# Sheet1.net
KiCad netlist of a schematic drawn in Altium Designer
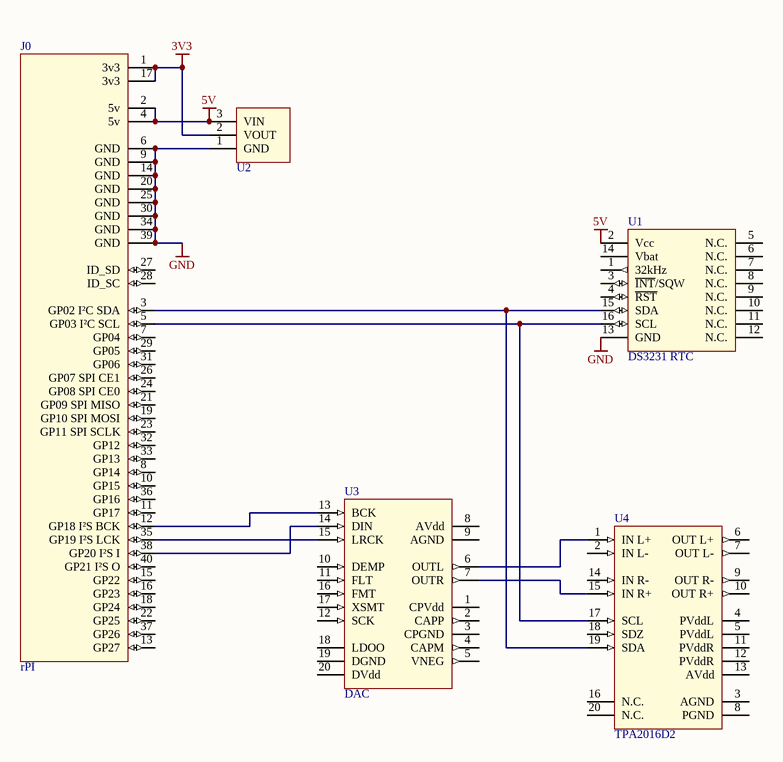
[diagram p0: Sheet1.SchDoc]

(export (version "E")
  (design (tool "Eeschema 10.0.6"))
  (components
    (comp (ref "J0")
      (value "rPI")
      (description "RaspberryPi 40 pin connector")
      (libsource (lib "Project") (part "RaspberryPi_40"))
    )
    (comp (ref "U1")
      (value "DS3231 RTC")
      (description "RTC build in Xtal")
      (libsource (lib "Project") (part "DS3231"))
    )
    (comp (ref "U2")
      (value "MCP1703T-3302E")
      (footprint "SOT-23A")
      (description "3v3 power reg")
      (libsource (lib "Project") (part "MCP1703T-3302E"))
    )
    (comp (ref "U3") (value "DAC") (description "PCM5102A DAC") (libsource (lib "Project") (part "PCM5102A")))
    (comp (ref "U4")
      (value "TPA2016D2")
      (description "I²C Controlled Audio Amplifier")
      (libsource (lib "Project") (part "TPA2016D2RTJR"))
    )
  )
  (nets
    (net (code "1") (name "3V3") (class "Default")
      (node (ref "J0") (pin "1") (pinfunction "3v3_1") (pintype "power_in"))
      (node (ref "J0") (pin "17") (pinfunction "3v3_17") (pintype "power_in"))
      (node (ref "U2") (pin "2") (pinfunction "VOUT_2") (pintype "power_in"))
    )
    (net (code "2") (name "5V") (class "Default")
      (node (ref "J0") (pin "2") (pinfunction "5v_2") (pintype "power_in"))
      (node (ref "J0") (pin "4") (pinfunction "5v_4") (pintype "power_in"))
      (node (ref "U1") (pin "2") (pinfunction "Vcc_2") (pintype "power_in"))
      (node (ref "U2") (pin "3") (pinfunction "VIN_3") (pintype "power_in"))
    )
    (net (code "3") (name "GND") (class "Default")
      (node (ref "J0") (pin "14") (pinfunction "GND_14") (pintype "power_in"))
      (node (ref "J0") (pin "20") (pinfunction "GND_20") (pintype "power_in"))
      (node (ref "J0") (pin "25") (pinfunction "GND_25") (pintype "power_in"))
      (node (ref "J0") (pin "30") (pinfunction "GND_30") (pintype "power_in"))
      (node (ref "J0") (pin "34") (pinfunction "GND_34") (pintype "power_in"))
      (node (ref "J0") (pin "39") (pinfunction "GND_39") (pintype "power_in"))
      (node (ref "J0") (pin "6") (pinfunction "GND_6") (pintype "power_in"))
      (node (ref "J0") (pin "9") (pinfunction "GND_9") (pintype "power_in"))
      (node (ref "U1") (pin "13") (pinfunction "GND_13") (pintype "power_in"))
      (node (ref "U2") (pin "1") (pinfunction "GND_1") (pintype "power_in"))
    )
    (net (code "4") (name "Net-(J0-GP02_I²C_SDA)") (class "Default")
      (node (ref "J0") (pin "3") (pinfunction "GP02_I²C_SDA_3") (pintype "bidirectional"))
      (node (ref "U1") (pin "15") (pinfunction "SDA_15") (pintype "bidirectional"))
      (node (ref "U4") (pin "19") (pinfunction "SDA_19") (pintype "input"))
    )
    (net (code "5") (name "Net-(J0-GP03_I²C_SCL)") (class "Default")
      (node (ref "J0") (pin "5") (pinfunction "GP03_I²C_SCL_5") (pintype "bidirectional"))
      (node (ref "U1") (pin "16") (pinfunction "SCL_16") (pintype "bidirectional"))
      (node (ref "U4") (pin "17") (pinfunction "SCL_17") (pintype "input"))
    )
    (net (code "6") (name "Net-(J0-GP18_I²S_BCK)") (class "Default")
      (node (ref "J0") (pin "12") (pinfunction "GP18_I²S_BCK_12") (pintype "bidirectional"))
      (node (ref "U3") (pin "13") (pinfunction "BCK_13") (pintype "input"))
    )
    (net (code "7") (name "Net-(J0-GP19_I²S_LCK)") (class "Default")
      (node (ref "J0") (pin "35") (pinfunction "GP19_I²S_LCK_35") (pintype "bidirectional"))
      (node (ref "U3") (pin "15") (pinfunction "LRCK_15") (pintype "input"))
    )
    (net (code "8") (name "Net-(J0-GP20_I²S_I)") (class "Default")
      (node (ref "J0") (pin "38") (pinfunction "GP20_I²S_I_38") (pintype "bidirectional"))
      (node (ref "U3") (pin "14") (pinfunction "DIN_14") (pintype "input"))
    )
    (net (code "9") (name "Net-(U3-OUTL)") (class "Default")
      (node (ref "U3") (pin "6") (pinfunction "OUTL_6") (pintype "output"))
      (node (ref "U4") (pin "1") (pinfunction "IN_L+_1") (pintype "input"))
    )
    (net (code "10") (name "Net-(U3-OUTR)") (class "Default")
      (node (ref "U3") (pin "7") (pinfunction "OUTR_7") (pintype "output"))
      (node (ref "U4") (pin "15") (pinfunction "IN_R+_15") (pintype "input"))
    )
    (net (code "11") (name "unconnected-(J0-GP04-Pad7)") (class "Default")
      (node (ref "J0") (pin "7") (pinfunction "GP04_7") (pintype "bidirectional"))
    )
    (net (code "12") (name "unconnected-(J0-GP05-Pad29)") (class "Default")
      (node (ref "J0") (pin "29") (pinfunction "GP05_29") (pintype "bidirectional"))
    )
    (net (code "13") (name "unconnected-(J0-GP06-Pad31)") (class "Default")
      (node (ref "J0") (pin "31") (pinfunction "GP06_31") (pintype "bidirectional"))
    )
    (net (code "14") (name "unconnected-(J0-GP07_SPI_CE1-Pad26)") (class "Default")
      (node (ref "J0") (pin "26") (pinfunction "GP07_SPI_CE1_26") (pintype "bidirectional"))
    )
    (net (code "15") (name "unconnected-(J0-GP08_SPI_CE0-Pad24)") (class "Default")
      (node (ref "J0") (pin "24") (pinfunction "GP08_SPI_CE0_24") (pintype "bidirectional"))
    )
    (net (code "16") (name "unconnected-(J0-GP09_SPI_MISO-Pad21)") (class "Default")
      (node (ref "J0") (pin "21") (pinfunction "GP09_SPI_MISO_21") (pintype "bidirectional"))
    )
    (net (code "17") (name "unconnected-(J0-GP10_SPI_MOSI-Pad19)") (class "Default")
      (node (ref "J0") (pin "19") (pinfunction "GP10_SPI_MOSI_19") (pintype "bidirectional"))
    )
    (net (code "18") (name "unconnected-(J0-GP11_SPI_SCLK-Pad23)") (class "Default")
      (node (ref "J0") (pin "23") (pinfunction "GP11_SPI_SCLK_23") (pintype "bidirectional"))
    )
    (net (code "19") (name "unconnected-(J0-GP12-Pad32)") (class "Default")
      (node (ref "J0") (pin "32") (pinfunction "GP12_32") (pintype "bidirectional"))
    )
    (net (code "20") (name "unconnected-(J0-GP13-Pad33)") (class "Default")
      (node (ref "J0") (pin "33") (pinfunction "GP13_33") (pintype "bidirectional"))
    )
    (net (code "21") (name "unconnected-(J0-GP14-Pad8)") (class "Default")
      (node (ref "J0") (pin "8") (pinfunction "GP14_8") (pintype "bidirectional"))
    )
    (net (code "22") (name "unconnected-(J0-GP15-Pad10)") (class "Default")
      (node (ref "J0") (pin "10") (pinfunction "GP15_10") (pintype "bidirectional"))
    )
    (net (code "23") (name "unconnected-(J0-GP16-Pad36)") (class "Default")
      (node (ref "J0") (pin "36") (pinfunction "GP16_36") (pintype "bidirectional"))
    )
    (net (code "24") (name "unconnected-(J0-GP17-Pad11)") (class "Default")
      (node (ref "J0") (pin "11") (pinfunction "GP17_11") (pintype "bidirectional"))
    )
    (net (code "25") (name "unconnected-(J0-GP21_I²S_O-Pad40)") (class "Default")
      (node (ref "J0") (pin "40") (pinfunction "GP21_I²S_O_40") (pintype "bidirectional"))
    )
    (net (code "26") (name "unconnected-(J0-GP22-Pad15)") (class "Default")
      (node (ref "J0") (pin "15") (pinfunction "GP22_15") (pintype "bidirectional"))
    )
    (net (code "27") (name "unconnected-(J0-GP23-Pad16)") (class "Default")
      (node (ref "J0") (pin "16") (pinfunction "GP23_16") (pintype "bidirectional"))
    )
    (net (code "28") (name "unconnected-(J0-GP24-Pad18)") (class "Default")
      (node (ref "J0") (pin "18") (pinfunction "GP24_18") (pintype "bidirectional"))
    )
    (net (code "29") (name "unconnected-(J0-GP25-Pad22)") (class "Default")
      (node (ref "J0") (pin "22") (pinfunction "GP25_22") (pintype "bidirectional"))
    )
    (net (code "30") (name "unconnected-(J0-GP26-Pad37)") (class "Default")
      (node (ref "J0") (pin "37") (pinfunction "GP26_37") (pintype "bidirectional"))
    )
    (net (code "31") (name "unconnected-(J0-GP27-Pad13)") (class "Default")
      (node (ref "J0") (pin "13") (pinfunction "GP27_13") (pintype "bidirectional"))
    )
    (net (code "32") (name "unconnected-(J0-ID_SC-Pad28)") (class "Default")
      (node (ref "J0") (pin "28") (pinfunction "ID_SC_28") (pintype "bidirectional"))
    )
    (net (code "33") (name "unconnected-(J0-ID_SD-Pad27)") (class "Default")
      (node (ref "J0") (pin "27") (pinfunction "ID_SD_27") (pintype "bidirectional"))
    )
    (net (code "34") (name "unconnected-(U1-32kHz-Pad1)") (class "Default")
      (node (ref "U1") (pin "1") (pinfunction "32kHz_1") (pintype "output"))
    )
    (net (code "35") (name "unconnected-(U1-N.C.-Pad5)") (class "Default")
      (node (ref "U1") (pin "5") (pinfunction "N.C._5") (pintype "passive"))
    )
    (net (code "36") (name "unconnected-(U1-N.C.-Pad6)") (class "Default")
      (node (ref "U1") (pin "6") (pinfunction "N.C._6") (pintype "passive"))
    )
    (net (code "37") (name "unconnected-(U1-N.C.-Pad7)") (class "Default")
      (node (ref "U1") (pin "7") (pinfunction "N.C._7") (pintype "passive"))
    )
    (net (code "38") (name "unconnected-(U1-N.C.-Pad8)") (class "Default")
      (node (ref "U1") (pin "8") (pinfunction "N.C._8") (pintype "passive"))
    )
    (net (code "39") (name "unconnected-(U1-N.C.-Pad9)") (class "Default")
      (node (ref "U1") (pin "9") (pinfunction "N.C._9") (pintype "passive"))
    )
    (net (code "40") (name "unconnected-(U1-N.C.-Pad10)") (class "Default")
      (node (ref "U1") (pin "10") (pinfunction "N.C._10") (pintype "passive"))
    )
    (net (code "41") (name "unconnected-(U1-N.C.-Pad11)") (class "Default")
      (node (ref "U1") (pin "11") (pinfunction "N.C._11") (pintype "passive"))
    )
    (net (code "42") (name "unconnected-(U1-N.C.-Pad12)") (class "Default")
      (node (ref "U1") (pin "12") (pinfunction "N.C._12") (pintype "passive"))
    )
    (net (code "43") (name "unconnected-(U1-Vbat-Pad14)") (class "Default")
      (node (ref "U1") (pin "14") (pinfunction "Vbat_14") (pintype "power_in"))
    )
    (net (code "44") (name "unconnected-(U1-~{INT}{slash}SQW-Pad3)") (class "Default")
      (node (ref "U1") (pin "3") (pinfunction "~{INT}/SQW_3") (pintype "bidirectional"))
    )
    (net (code "45") (name "unconnected-(U1-~{RST}-Pad4)") (class "Default")
      (node (ref "U1") (pin "4") (pinfunction "~{RST}_4") (pintype "bidirectional"))
    )
    (net (code "46") (name "unconnected-(U3-AGND-Pad9)") (class "Default")
      (node (ref "U3") (pin "9") (pinfunction "AGND_9") (pintype "power_in"))
    )
    (net (code "47") (name "unconnected-(U3-AVdd-Pad8)") (class "Default")
      (node (ref "U3") (pin "8") (pinfunction "AVdd_8") (pintype "power_in"))
    )
    (net (code "48") (name "unconnected-(U3-CAPM-Pad4)") (class "Default")
      (node (ref "U3") (pin "4") (pinfunction "CAPM_4") (pintype "output"))
    )
    (net (code "49") (name "unconnected-(U3-CAPP-Pad2)") (class "Default")
      (node (ref "U3") (pin "2") (pinfunction "CAPP_2") (pintype "output"))
    )
    (net (code "50") (name "unconnected-(U3-CPGND-Pad3)") (class "Default")
      (node (ref "U3") (pin "3") (pinfunction "CPGND_3") (pintype "passive"))
    )
    (net (code "51") (name "unconnected-(U3-CPVdd-Pad1)") (class "Default")
      (node (ref "U3") (pin "1") (pinfunction "CPVdd_1") (pintype "power_in"))
    )
    (net (code "52") (name "unconnected-(U3-DEMP-Pad10)") (class "Default")
      (node (ref "U3") (pin "10") (pinfunction "DEMP_10") (pintype "input"))
    )
    (net (code "53") (name "unconnected-(U3-DGND-Pad19)") (class "Default")
      (node (ref "U3") (pin "19") (pinfunction "DGND_19") (pintype "power_in"))
    )
    (net (code "54") (name "unconnected-(U3-DVdd-Pad20)") (class "Default")
      (node (ref "U3") (pin "20") (pinfunction "DVdd_20") (pintype "power_in"))
    )
    (net (code "55") (name "unconnected-(U3-FLT-Pad11)") (class "Default")
      (node (ref "U3") (pin "11") (pinfunction "FLT_11") (pintype "input"))
    )
    (net (code "56") (name "unconnected-(U3-FMT-Pad16)") (class "Default")
      (node (ref "U3") (pin "16") (pinfunction "FMT_16") (pintype "input"))
    )
    (net (code "57") (name "unconnected-(U3-LDOO-Pad18)") (class "Default")
      (node (ref "U3") (pin "18") (pinfunction "LDOO_18") (pintype "passive"))
    )
    (net (code "58") (name "unconnected-(U3-SCK-Pad12)") (class "Default")
      (node (ref "U3") (pin "12") (pinfunction "SCK_12") (pintype "input"))
    )
    (net (code "59") (name "unconnected-(U3-VNEG-Pad5)") (class "Default")
      (node (ref "U3") (pin "5") (pinfunction "VNEG_5") (pintype "output"))
    )
    (net (code "60") (name "unconnected-(U3-XSMT-Pad17)") (class "Default")
      (node (ref "U3") (pin "17") (pinfunction "XSMT_17") (pintype "input"))
    )
    (net (code "61") (name "unconnected-(U4-AGND-Pad3)") (class "Default")
      (node (ref "U4") (pin "3") (pinfunction "AGND_3") (pintype "power_in"))
    )
    (net (code "62") (name "unconnected-(U4-AVdd-Pad13)") (class "Default")
      (node (ref "U4") (pin "13") (pinfunction "AVdd_13") (pintype "power_in"))
    )
    (net (code "63") (name "unconnected-(U4-IN_L--Pad2)") (class "Default")
      (node (ref "U4") (pin "2") (pinfunction "IN_L-_2") (pintype "input"))
    )
    (net (code "64") (name "unconnected-(U4-IN_R--Pad14)") (class "Default")
      (node (ref "U4") (pin "14") (pinfunction "IN_R-_14") (pintype "input"))
    )
    (net (code "65") (name "unconnected-(U4-N.C.-Pad16)") (class "Default")
      (node (ref "U4") (pin "16") (pinfunction "N.C._16") (pintype "power_in"))
    )
    (net (code "66") (name "unconnected-(U4-N.C.-Pad20)") (class "Default")
      (node (ref "U4") (pin "20") (pinfunction "N.C._20") (pintype "power_in"))
    )
    (net (code "67") (name "unconnected-(U4-OUT_L+-Pad6)") (class "Default")
      (node (ref "U4") (pin "6") (pinfunction "OUT_L+_6") (pintype "output"))
    )
    (net (code "68") (name "unconnected-(U4-OUT_L--Pad7)") (class "Default")
      (node (ref "U4") (pin "7") (pinfunction "OUT_L-_7") (pintype "output"))
    )
    (net (code "69") (name "unconnected-(U4-OUT_R+-Pad10)") (class "Default")
      (node (ref "U4") (pin "10") (pinfunction "OUT_R+_10") (pintype "output"))
    )
    (net (code "70") (name "unconnected-(U4-OUT_R--Pad9)") (class "Default")
      (node (ref "U4") (pin "9") (pinfunction "OUT_R-_9") (pintype "output"))
    )
    (net (code "71") (name "unconnected-(U4-PGND-Pad8)") (class "Default")
      (node (ref "U4") (pin "8") (pinfunction "PGND_8") (pintype "power_in"))
    )
    (net (code "72") (name "unconnected-(U4-PVddL-Pad4)") (class "Default")
      (node (ref "U4") (pin "4") (pinfunction "PVddL_4") (pintype "power_in"))
    )
    (net (code "73") (name "unconnected-(U4-PVddL-Pad5)") (class "Default")
      (node (ref "U4") (pin "5") (pinfunction "PVddL_5") (pintype "power_in"))
    )
    (net (code "74") (name "unconnected-(U4-PVddR-Pad11)") (class "Default")
      (node (ref "U4") (pin "11") (pinfunction "PVddR_11") (pintype "power_in"))
    )
    (net (code "75") (name "unconnected-(U4-PVddR-Pad12)") (class "Default")
      (node (ref "U4") (pin "12") (pinfunction "PVddR_12") (pintype "power_in"))
    )
    (net (code "76") (name "unconnected-(U4-SDZ-Pad18)") (class "Default")
      (node (ref "U4") (pin "18") (pinfunction "SDZ_18") (pintype "input"))
    )
  )
)
